# PF5d_Filter2B.net
KiCad netlist of a schematic drawn in Altium Designer
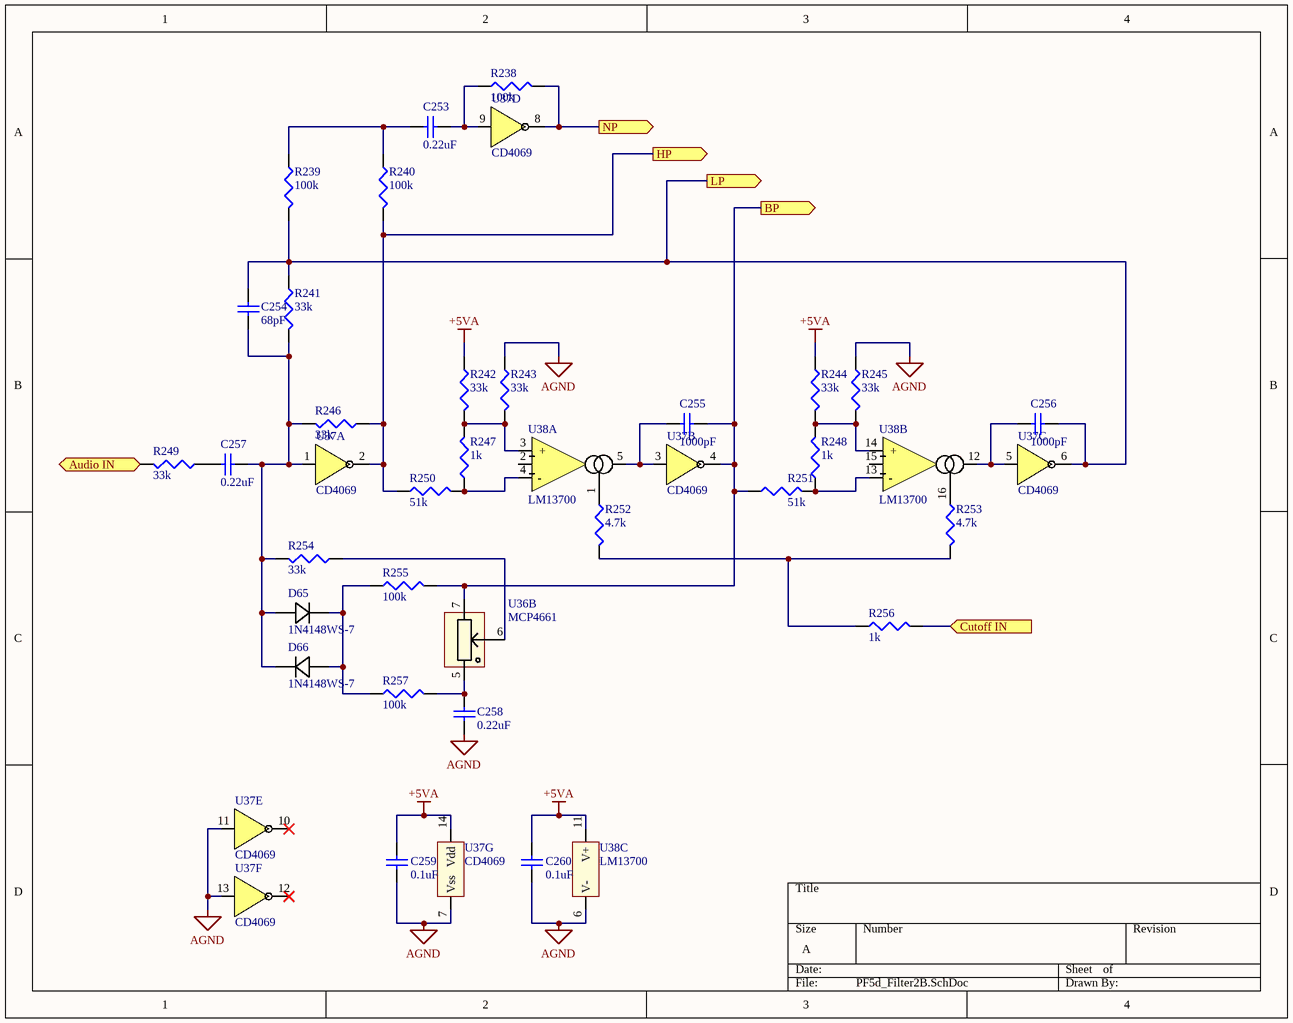
[diagram p0: PF5d_Filter2B.SchDoc]

(export (version "E")
  (design (tool "Eeschema 10.0.6"))
  (components
    (comp (ref "C253")
      (value "0.22uF")
      (footprint "CAPC1608X08")
      (description "Capacitor (Semiconductor SIM Model)")
      (libsource (lib "Michel") (part "Cap Semi"))
    )
    (comp (ref "C254")
      (value "68pF")
      (footprint "CAPC1608X08")
      (description "Capacitor (Semiconductor SIM Model)")
      (libsource (lib "Michel") (part "Cap Semi"))
    )
    (comp (ref "C255")
      (value "1000pF")
      (footprint "CAPC1608X08")
      (description "Capacitor (Semiconductor SIM Model)")
      (libsource (lib "Michel") (part "Cap Semi"))
    )
    (comp (ref "C256")
      (value "1000pF")
      (footprint "CAPC1608X08")
      (description "Capacitor (Semiconductor SIM Model)")
      (libsource (lib "Michel") (part "Cap Semi"))
    )
    (comp (ref "C257")
      (value "0.22uF")
      (footprint "CAPC1608X08")
      (description "Capacitor (Semiconductor SIM Model)")
      (libsource (lib "Michel") (part "Cap Semi"))
    )
    (comp (ref "C258")
      (value "0.22uF")
      (footprint "CAPC1608X08")
      (description "Capacitor (Semiconductor SIM Model)")
      (libsource (lib "Michel") (part "Cap Semi"))
    )
    (comp (ref "C259")
      (value "0.1uF")
      (footprint "CAPC1608X08")
      (description "Capacitor (Semiconductor SIM Model)")
      (libsource (lib "Michel") (part "Cap Semi"))
    )
    (comp (ref "C260")
      (value "0.1uF")
      (footprint "CAPC1608X08")
      (description "Capacitor (Semiconductor SIM Model)")
      (libsource (lib "Michel") (part "Cap Semi"))
    )
    (comp (ref "D65")
      (value "1N4148WS-7")
      (footprint "SOD323-M")
      (description "Diode signaux faibles")
      (libsource (lib "Michel") (part "1N4148WS-7"))
    )
    (comp (ref "D66")
      (value "1N4148WS-7")
      (footprint "SOD323-M")
      (description "Diode signaux faibles")
      (libsource (lib "Michel") (part "1N4148WS-7"))
    )
    (comp (ref "R238")
      (value "100k")
      (footprint "RESC1608X05")
      (description "Resistor")
      (libsource (lib "Michel") (part "Res3"))
    )
    (comp (ref "R239")
      (value "100k")
      (footprint "RESC1608X05")
      (description "Resistor")
      (libsource (lib "Michel") (part "Res3"))
    )
    (comp (ref "R240")
      (value "100k")
      (footprint "RESC1608X05")
      (description "Resistor")
      (libsource (lib "Michel") (part "Res3"))
    )
    (comp (ref "R241")
      (value "33k")
      (footprint "RESC1608X05")
      (description "Resistor")
      (libsource (lib "Michel") (part "Res3"))
    )
    (comp (ref "R242")
      (value "33k")
      (footprint "RESC1608X05")
      (description "Resistor")
      (libsource (lib "Michel") (part "Res3"))
    )
    (comp (ref "R243")
      (value "33k")
      (footprint "RESC1608X05")
      (description "Resistor")
      (libsource (lib "Michel") (part "Res3"))
    )
    (comp (ref "R244")
      (value "33k")
      (footprint "RESC1608X05")
      (description "Resistor")
      (libsource (lib "Michel") (part "Res3"))
    )
    (comp (ref "R245")
      (value "33k")
      (footprint "RESC1608X05")
      (description "Resistor")
      (libsource (lib "Michel") (part "Res3"))
    )
    (comp (ref "R246")
      (value "33k")
      (footprint "RESC1608X05")
      (description "Resistor")
      (libsource (lib "Michel") (part "Res3"))
    )
    (comp (ref "R247")
      (value "1k")
      (footprint "RESC1608X05")
      (description "Resistor")
      (libsource (lib "Michel") (part "Res3"))
    )
    (comp (ref "R248")
      (value "1k")
      (footprint "RESC1608X05")
      (description "Resistor")
      (libsource (lib "Michel") (part "Res3"))
    )
    (comp (ref "R249")
      (value "33k")
      (footprint "RESC1608X05")
      (description "Resistor")
      (libsource (lib "Michel") (part "Res3"))
    )
    (comp (ref "R250")
      (value "51k")
      (footprint "RESC1608X05")
      (description "Resistor")
      (libsource (lib "Michel") (part "Res3"))
    )
    (comp (ref "R251")
      (value "51k")
      (footprint "RESC1608X05")
      (description "Resistor")
      (libsource (lib "Michel") (part "Res3"))
    )
    (comp (ref "R252")
      (value "4.7k")
      (footprint "RESC1608X05")
      (description "Resistor")
      (libsource (lib "Michel") (part "Res3"))
    )
    (comp (ref "R253")
      (value "4.7k")
      (footprint "RESC1608X05")
      (description "Resistor")
      (libsource (lib "Michel") (part "Res3"))
    )
    (comp (ref "R254")
      (value "33k")
      (footprint "RESC1608X05")
      (description "Resistor")
      (libsource (lib "Michel") (part "Res3"))
    )
    (comp (ref "R255")
      (value "100k")
      (footprint "RESC1608X05")
      (description "Resistor")
      (libsource (lib "Michel") (part "Res3"))
    )
    (comp (ref "R256")
      (value "1k")
      (footprint "RESC1608X05")
      (description "Resistor")
      (libsource (lib "Michel") (part "Res3"))
    )
    (comp (ref "R257")
      (value "100k")
      (footprint "RESC1608X05")
      (description "Resistor")
      (libsource (lib "Michel") (part "Res3"))
    )
    (comp (ref "U36")
      (value "MCP4661")
      (footprint "TSSOP14_MC-M")
      (description "Dual DigiPot non volatile I2C")
      (libsource (lib "Michel") (part "MCP4661"))
    )
    (comp (ref "U37")
      (value "CD4069")
      (footprint "D14-M")
      (description "Hex Inverter")
      (libsource (lib "Michel") (part "CD4069"))
    )
    (comp (ref "U38")
      (value "LM13700")
      (footprint "SO16NB")
      (description "Dual Transconductance OpAmp")
      (libsource (lib "Michel") (part "LM13700M"))
    )
  )
  (nets
    (net (code "1") (name "+5VA") (class "Default")
      (node (ref "C259") (pin "1") (pinfunction "1_1") (pintype "passive"))
      (node (ref "C260") (pin "1") (pinfunction "1_1") (pintype "passive"))
      (node (ref "R242") (pin "1") (pinfunction "1_1") (pintype "passive"))
      (node (ref "R244") (pin "1") (pinfunction "1_1") (pintype "passive"))
      (node (ref "U37") (pin "14") (pinfunction "Vdd_14") (pintype "power_in"))
      (node (ref "U38") (pin "11") (pinfunction "V+_11") (pintype "power_in"))
    )
    (net (code "2") (name "/Audio IN") (class "Default")
      (node (ref "R249") (pin "2") (pinfunction "2_2") (pintype "passive"))
    )
    (net (code "3") (name "/BP") (class "Default")
      (node (ref "C255") (pin "2") (pinfunction "2_2") (pintype "passive"))
      (node (ref "R251") (pin "1") (pinfunction "1_1") (pintype "passive"))
      (node (ref "R255") (pin "2") (pinfunction "2_2") (pintype "passive"))
      (node (ref "U36") (pin "7") (pinfunction "P1A_7") (pintype "passive"))
      (node (ref "U37") (pin "4") (pinfunction "~{B}_4") (pintype "passive"))
    )
    (net (code "4") (name "/Cutoff IN") (class "Default")
      (node (ref "R256") (pin "2") (pinfunction "2_2") (pintype "passive"))
    )
    (net (code "5") (name "/HP") (class "Default")
      (node (ref "R240") (pin "2") (pinfunction "2_2") (pintype "passive"))
      (node (ref "R246") (pin "1") (pinfunction "1_1") (pintype "passive"))
      (node (ref "R250") (pin "1") (pinfunction "1_1") (pintype "passive"))
      (node (ref "U37") (pin "2") (pinfunction "~{A}_2") (pintype "passive"))
    )
    (net (code "6") (name "/LP") (class "Default")
      (node (ref "C254") (pin "2") (pinfunction "2_2") (pintype "passive"))
      (node (ref "C256") (pin "2") (pinfunction "2_2") (pintype "passive"))
      (node (ref "R239") (pin "2") (pinfunction "2_2") (pintype "passive"))
      (node (ref "R241") (pin "1") (pinfunction "1_1") (pintype "passive"))
      (node (ref "U37") (pin "6") (pinfunction "~{C}_6") (pintype "passive"))
    )
    (net (code "7") (name "/NP") (class "Default")
      (node (ref "R238") (pin "2") (pinfunction "2_2") (pintype "passive"))
      (node (ref "U37") (pin "8") (pinfunction "~{D}_8") (pintype "passive"))
    )
    (net (code "8") (name "AGND") (class "Default")
      (node (ref "C258") (pin "2") (pinfunction "2_2") (pintype "passive"))
      (node (ref "C259") (pin "2") (pinfunction "2_2") (pintype "passive"))
      (node (ref "C260") (pin "2") (pinfunction "2_2") (pintype "passive"))
      (node (ref "R243") (pin "1") (pinfunction "1_1") (pintype "passive"))
      (node (ref "R245") (pin "1") (pinfunction "1_1") (pintype "passive"))
      (node (ref "U37") (pin "11") (pinfunction "E_11") (pintype "passive"))
      (node (ref "U37") (pin "13") (pinfunction "F_13") (pintype "passive"))
      (node (ref "U37") (pin "7") (pinfunction "Vss_7") (pintype "power_in"))
      (node (ref "U38") (pin "6") (pinfunction "V-_6") (pintype "power_in"))
    )
    (net (code "9") (name "Net-(C253-Pad2)") (class "Default")
      (node (ref "C253") (pin "2") (pinfunction "2_2") (pintype "passive"))
      (node (ref "R239") (pin "1") (pinfunction "1_1") (pintype "passive"))
      (node (ref "R240") (pin "1") (pinfunction "1_1") (pintype "passive"))
    )
    (net (code "10") (name "Net-(C257-Pad2)") (class "Default")
      (node (ref "C257") (pin "2") (pinfunction "2_2") (pintype "passive"))
      (node (ref "R249") (pin "1") (pinfunction "1_1") (pintype "passive"))
    )
    (net (code "11") (name "Net-(D65-Pad1)") (class "Default")
      (node (ref "D65") (pin "1") (pinfunction "1_1") (pintype "passive"))
      (node (ref "D66") (pin "2") (pinfunction "2_2") (pintype "passive"))
      (node (ref "R255") (pin "1") (pinfunction "1_1") (pintype "passive"))
      (node (ref "R257") (pin "1") (pinfunction "1_1") (pintype "passive"))
    )
    (net (code "12") (name "Net-(R252-Pad2)") (class "Default")
      (node (ref "R252") (pin "2") (pinfunction "2_2") (pintype "passive"))
      (node (ref "R253") (pin "2") (pinfunction "2_2") (pintype "passive"))
      (node (ref "R256") (pin "1") (pinfunction "1_1") (pintype "passive"))
    )
    (net (code "13") (name "Net-(U36B-P1B)") (class "Default")
      (node (ref "C258") (pin "1") (pinfunction "1_1") (pintype "passive"))
      (node (ref "R257") (pin "2") (pinfunction "2_2") (pintype "passive"))
      (node (ref "U36") (pin "5") (pinfunction "P1B_5") (pintype "passive"))
    )
    (net (code "14") (name "Net-(U36B-P1W)") (class "Default")
      (node (ref "R254") (pin "1") (pinfunction "1_1") (pintype "passive"))
      (node (ref "U36") (pin "6") (pinfunction "P1W_6") (pintype "passive"))
    )
    (net (code "15") (name "Net-(U37A-A)") (class "Default")
      (node (ref "C254") (pin "1") (pinfunction "1_1") (pintype "passive"))
      (node (ref "C257") (pin "1") (pinfunction "1_1") (pintype "passive"))
      (node (ref "D65") (pin "2") (pinfunction "2_2") (pintype "passive"))
      (node (ref "D66") (pin "1") (pinfunction "1_1") (pintype "passive"))
      (node (ref "R241") (pin "2") (pinfunction "2_2") (pintype "passive"))
      (node (ref "R246") (pin "2") (pinfunction "2_2") (pintype "passive"))
      (node (ref "R254") (pin "2") (pinfunction "2_2") (pintype "passive"))
      (node (ref "U37") (pin "1") (pinfunction "A_1") (pintype "passive"))
    )
    (net (code "16") (name "Net-(U37B-B)") (class "Default")
      (node (ref "C255") (pin "1") (pinfunction "1_1") (pintype "passive"))
      (node (ref "U37") (pin "3") (pinfunction "B_3") (pintype "passive"))
      (node (ref "U38") (pin "5") (pinfunction "OUT_5") (pintype "passive"))
    )
    (net (code "17") (name "Net-(U37C-C)") (class "Default")
      (node (ref "C256") (pin "1") (pinfunction "1_1") (pintype "passive"))
      (node (ref "U37") (pin "5") (pinfunction "C_5") (pintype "passive"))
      (node (ref "U38") (pin "12") (pinfunction "OUT_12") (pintype "passive"))
    )
    (net (code "18") (name "Net-(U37D-D)") (class "Default")
      (node (ref "C253") (pin "1") (pinfunction "1_1") (pintype "passive"))
      (node (ref "R238") (pin "1") (pinfunction "1_1") (pintype "passive"))
      (node (ref "U37") (pin "9") (pinfunction "D_9") (pintype "passive"))
    )
    (net (code "19") (name "Net-(U38A-+)") (class "Default")
      (node (ref "R242") (pin "2") (pinfunction "2_2") (pintype "passive"))
      (node (ref "R243") (pin "2") (pinfunction "2_2") (pintype "passive"))
      (node (ref "R247") (pin "2") (pinfunction "2_2") (pintype "passive"))
      (node (ref "U38") (pin "3") (pinfunction "+_3") (pintype "passive"))
    )
    (net (code "20") (name "Net-(U38A--)") (class "Default")
      (node (ref "R247") (pin "1") (pinfunction "1_1") (pintype "passive"))
      (node (ref "R250") (pin "2") (pinfunction "2_2") (pintype "passive"))
      (node (ref "U38") (pin "4") (pinfunction "-_4") (pintype "passive"))
    )
    (net (code "21") (name "Net-(U38A-BIAS)") (class "Default")
      (node (ref "R252") (pin "1") (pinfunction "1_1") (pintype "passive"))
      (node (ref "U38") (pin "1") (pinfunction "BIAS_1") (pintype "passive"))
    )
    (net (code "22") (name "Net-(U38B-+)") (class "Default")
      (node (ref "R244") (pin "2") (pinfunction "2_2") (pintype "passive"))
      (node (ref "R245") (pin "2") (pinfunction "2_2") (pintype "passive"))
      (node (ref "R248") (pin "2") (pinfunction "2_2") (pintype "passive"))
      (node (ref "U38") (pin "14") (pinfunction "+_14") (pintype "passive"))
    )
    (net (code "23") (name "Net-(U38B--)") (class "Default")
      (node (ref "R248") (pin "1") (pinfunction "1_1") (pintype "passive"))
      (node (ref "R251") (pin "2") (pinfunction "2_2") (pintype "passive"))
      (node (ref "U38") (pin "13") (pinfunction "-_13") (pintype "passive"))
    )
    (net (code "24") (name "Net-(U38B-BIAS)") (class "Default")
      (node (ref "R253") (pin "1") (pinfunction "1_1") (pintype "passive"))
      (node (ref "U38") (pin "16") (pinfunction "BIAS_16") (pintype "passive"))
    )
    (net (code "25") (name "unconnected-(U37E-~{E}-Pad10)") (class "Default")
      (node (ref "U37") (pin "10") (pinfunction "~{E}_10") (pintype "passive+no_connect"))
    )
    (net (code "26") (name "unconnected-(U37F-~{F}-Pad12)") (class "Default")
      (node (ref "U37") (pin "12") (pinfunction "~{F}_12") (pintype "passive+no_connect"))
    )
    (net (code "27") (name "unconnected-(U38A-Diode_BIAS-Pad2)") (class "Default")
      (node (ref "U38") (pin "2") (pinfunction "Diode_BIAS_2") (pintype "passive"))
    )
    (net (code "28") (name "unconnected-(U38B-Diode_BIAS-Pad15)") (class "Default")
      (node (ref "U38") (pin "15") (pinfunction "Diode_BIAS_15") (pintype "passive"))
    )
  )
)
